# Ethernet_Phy.net
KiCad netlist of a schematic drawn in Altium Designer
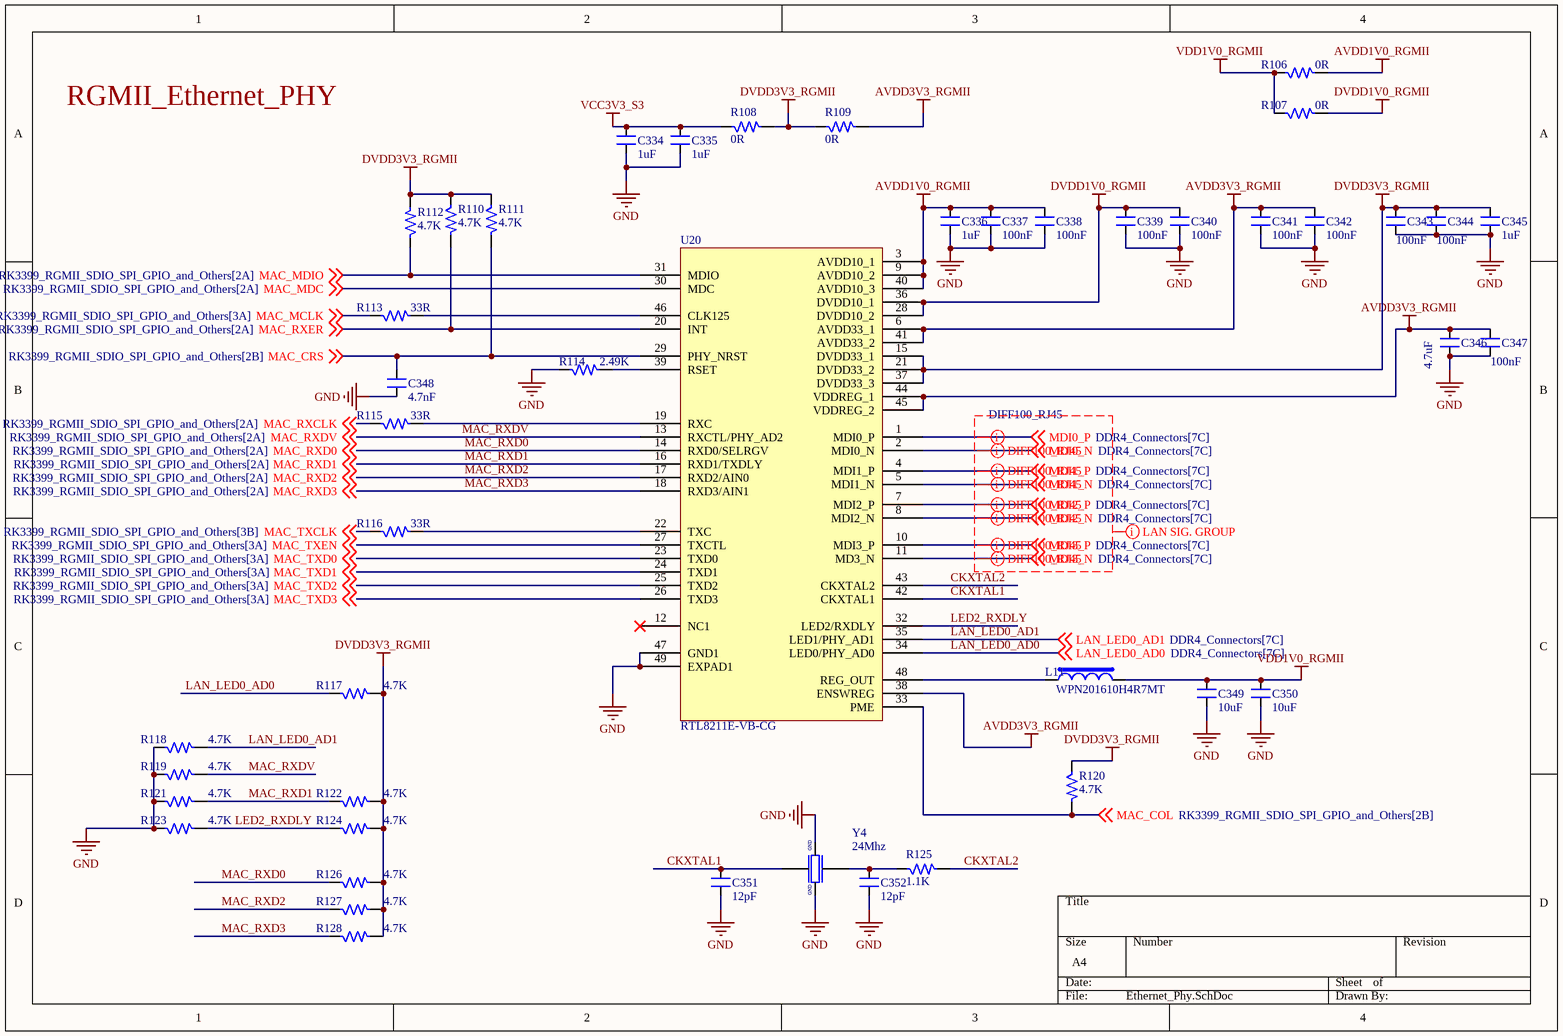
[diagram p0: Ethernet_Phy.SchDoc]

(export (version "E")
  (design (tool "Eeschema 10.0.6"))
  (components
    (comp (ref "C334")
      (value "1uF")
      (footprint "CAP_0201")
      (description "1µF ±20% 16V Ceramic Capacitor X5R 0201 (0603 Metric)")
      (fields
        (field (name "MANUFACTURER") "Samsung Electro-Mechanics")
        (field (name "MANUFACTURER PART NUMBER") "CL03A105MO3NRNH")
      )
      (libsource (lib "EsteemPCB_SOM_Course_schlib") (part "CAP_1uF-16V-10%-0201"))
    )
    (comp (ref "C335")
      (value "1uF")
      (footprint "CAP_0201")
      (description "1µF ±20% 16V Ceramic Capacitor X5R 0201 (0603 Metric)")
      (fields
        (field (name "MANUFACTURER") "Samsung Electro-Mechanics")
        (field (name "MANUFACTURER PART NUMBER") "CL03A105MO3NRNH")
      )
      (libsource (lib "EsteemPCB_SOM_Course_schlib") (part "CAP_1uF-16V-10%-0201"))
    )
    (comp (ref "C336")
      (value "1uF")
      (footprint "CAP_0201")
      (description "1µF ±20% 16V Ceramic Capacitor X5R 0201 (0603 Metric)")
      (fields
        (field (name "MANUFACTURER") "Samsung Electro-Mechanics")
        (field (name "MANUFACTURER PART NUMBER") "CL03A105MO3NRNH")
      )
      (libsource (lib "EsteemPCB_SOM_Course_schlib") (part "CAP_1uF-16V-10%-0201"))
    )
    (comp (ref "C337")
      (value "100nF")
      (footprint "CAP_0201")
      (description "0.1µF ±10% 25V Ceramic Capacitor X5R 0201 (0603 Metric)")
      (fields
        (field (name "MANUFACTURER") "TDK Corporation")
        (field (name "MANUFACTURER PART NUMBER") "C0603X5R1E104K030BB")
      )
      (libsource (lib "EsteemPCB_SOM_Course_schlib") (part "CAP_100nF-25V-10%-0201"))
    )
    (comp (ref "C338")
      (value "100nF")
      (footprint "CAP_0201")
      (description "0.1µF ±10% 25V Ceramic Capacitor X5R 0201 (0603 Metric)")
      (fields
        (field (name "MANUFACTURER") "TDK Corporation")
        (field (name "MANUFACTURER PART NUMBER") "C0603X5R1E104K030BB")
      )
      (libsource (lib "EsteemPCB_SOM_Course_schlib") (part "CAP_100nF-25V-10%-0201"))
    )
    (comp (ref "C339")
      (value "100nF")
      (footprint "CAP_0201")
      (description "0.1µF ±10% 25V Ceramic Capacitor X5R 0201 (0603 Metric)")
      (fields
        (field (name "MANUFACTURER") "TDK Corporation")
        (field (name "MANUFACTURER PART NUMBER") "C0603X5R1E104K030BB")
      )
      (libsource (lib "EsteemPCB_SOM_Course_schlib") (part "CAP_100nF-25V-10%-0201"))
    )
    (comp (ref "C340")
      (value "100nF")
      (footprint "CAP_0201")
      (description "0.1µF ±10% 25V Ceramic Capacitor X5R 0201 (0603 Metric)")
      (fields
        (field (name "MANUFACTURER") "TDK Corporation")
        (field (name "MANUFACTURER PART NUMBER") "C0603X5R1E104K030BB")
      )
      (libsource (lib "EsteemPCB_SOM_Course_schlib") (part "CAP_100nF-25V-10%-0201"))
    )
    (comp (ref "C341")
      (value "100nF")
      (footprint "CAP_0201")
      (description "0.1µF ±10% 25V Ceramic Capacitor X5R 0201 (0603 Metric)")
      (fields
        (field (name "MANUFACTURER") "TDK Corporation")
        (field (name "MANUFACTURER PART NUMBER") "C0603X5R1E104K030BB")
      )
      (libsource (lib "EsteemPCB_SOM_Course_schlib") (part "CAP_100nF-25V-10%-0201"))
    )
    (comp (ref "C342")
      (value "100nF")
      (footprint "CAP_0201")
      (description "0.1µF ±10% 25V Ceramic Capacitor X5R 0201 (0603 Metric)")
      (fields
        (field (name "MANUFACTURER") "TDK Corporation")
        (field (name "MANUFACTURER PART NUMBER") "C0603X5R1E104K030BB")
      )
      (libsource (lib "EsteemPCB_SOM_Course_schlib") (part "CAP_100nF-25V-10%-0201"))
    )
    (comp (ref "C343")
      (value "100nF")
      (footprint "CAP_0201")
      (description "0.1µF ±10% 25V Ceramic Capacitor X5R 0201 (0603 Metric)")
      (fields
        (field (name "MANUFACTURER") "TDK Corporation")
        (field (name "MANUFACTURER PART NUMBER") "C0603X5R1E104K030BB")
      )
      (libsource (lib "EsteemPCB_SOM_Course_schlib") (part "CAP_100nF-25V-10%-0201"))
    )
    (comp (ref "C344")
      (value "100nF")
      (footprint "CAP_0201")
      (description "0.1µF ±10% 25V Ceramic Capacitor X5R 0201 (0603 Metric)")
      (fields
        (field (name "MANUFACTURER") "TDK Corporation")
        (field (name "MANUFACTURER PART NUMBER") "C0603X5R1E104K030BB")
      )
      (libsource (lib "EsteemPCB_SOM_Course_schlib") (part "CAP_100nF-25V-10%-0201"))
    )
    (comp (ref "C345")
      (value "1uF")
      (footprint "CAP_0201")
      (description "1µF ±20% 16V Ceramic Capacitor X5R 0201 (0603 Metric)")
      (fields
        (field (name "MANUFACTURER") "Samsung Electro-Mechanics")
        (field (name "MANUFACTURER PART NUMBER") "CL03A105MO3NRNH")
      )
      (libsource (lib "EsteemPCB_SOM_Course_schlib") (part "CAP_1uF-16V-10%-0201"))
    )
    (comp (ref "C346")
      (value "4.7uF")
      (footprint "CAP_0201")
      (description "4.7µF ±20% 6.3V Ceramic Capacitor X5R 0201 (0603 Metric)")
      (fields
        (field (name "MANUFACTURER") "Murata Electronics")
        (field (name "MANUFACTURER PART NUMBER") "GRM035R60J475ME15D")
      )
      (libsource (lib "EsteemPCB_SOM_Course_schlib") (part "CAP_4.7uF-6.3V-20%-0201"))
    )
    (comp (ref "C347")
      (value "100nF")
      (footprint "CAP_0201")
      (description "0.1µF ±10% 25V Ceramic Capacitor X5R 0201 (0603 Metric)")
      (fields
        (field (name "MANUFACTURER") "TDK Corporation")
        (field (name "MANUFACTURER PART NUMBER") "C0603X5R1E104K030BB")
      )
      (libsource (lib "EsteemPCB_SOM_Course_schlib") (part "CAP_100nF-25V-10%-0201"))
    )
    (comp (ref "C348")
      (value "4.7nF")
      (footprint "CAP_0201")
      (description "4700pF ±10% 10V Ceramic Capacitor X7R 0201 (0603 Metric)")
      (fields
        (field (name "MANUFACTURER") "AVX Corporation")
        (field (name "MANUFACTURER PART NUMBER") "0201ZC472KAT2A")
      )
      (libsource (lib "EsteemPCB_SOM_Course_schlib") (part "CAP_4.7nF-10V-10%-0201"))
    )
    (comp (ref "C349")
      (value "10uF")
      (footprint "CAP_0402")
      (description "10µF ±20% 10V Ceramic Capacitor X5R 0402 (1005 Metric)")
      (fields
        (field (name "MANUFACTURER PART NUMBER") "CL05A106MP5NUNC")
        (field (name "MANUFACTURER") "Samsung Electro-Mechanics")
      )
      (libsource (lib "EsteemPCB_SOM_Course_schlib") (part "CAP_10uF-10V-20%-0402"))
    )
    (comp (ref "C350")
      (value "10uF")
      (footprint "CAP_0402")
      (description "10µF ±20% 10V Ceramic Capacitor X5R 0402 (1005 Metric)")
      (fields
        (field (name "MANUFACTURER PART NUMBER") "CL05A106MP5NUNC")
        (field (name "MANUFACTURER") "Samsung Electro-Mechanics")
      )
      (libsource (lib "EsteemPCB_SOM_Course_schlib") (part "CAP_10uF-10V-20%-0402"))
    )
    (comp (ref "C351")
      (value "12pF")
      (footprint "CAP_0201")
      (description "12pF ±10% 16V Ceramic Capacitor C0G, NP0 0201 (0603 Metric)")
      (fields
        (field (name "MANUFACTURER") "AVX Corporation")
        (field (name "MANUFACTURER PART NUMBER") "0201YA120KAT2A")
      )
      (libsource (lib "EsteemPCB_SOM_Course_schlib") (part "CAP_12pF-16V-10%-0201"))
    )
    (comp (ref "C352")
      (value "12pF")
      (footprint "CAP_0201")
      (description "12pF ±10% 16V Ceramic Capacitor C0G, NP0 0201 (0603 Metric)")
      (fields
        (field (name "MANUFACTURER") "AVX Corporation")
        (field (name "MANUFACTURER PART NUMBER") "0201YA120KAT2A")
      )
      (libsource (lib "EsteemPCB_SOM_Course_schlib") (part "CAP_12pF-16V-10%-0201"))
    )
    (comp (ref "L11")
      (value "WPN201610H4R7MT")
      (footprint "IND_62.9_110X86.6_SMD")
      (description "4.7uH ±20% 900mA 425mΩ SMD,2.0x1.6x1.0mm Power Inductors RoHS")
      (fields (field (name "MANUFACTURER") "Sunlord"))
      (libsource (lib "EsteemPCB_SOM_Course_schlib") (part "IND_4.7uH-0.9A-20%-SMD"))
    )
    (comp (ref "R106")
      (value "0R")
      (footprint "RES_0201")
      (description "0 Ohms Jumper 0.05W, 1/20W Chip Resistor 0201 (0603 Metric) Automotive AEC-Q200 Thick Film")
      (fields
        (field (name "MANUFACTURER") "Bourns Inc.")
        (field (name "MANUFACTURER PART NUMBER") "CR0201AJ/-000GLF")
      )
      (libsource (lib "EsteemPCB_SOM_Course_schlib") (part "RES_0R-0.05W-1%-0201"))
    )
    (comp (ref "R107")
      (value "0R")
      (footprint "RES_0201")
      (description "0 Ohms Jumper 0.05W, 1/20W Chip Resistor 0201 (0603 Metric) Automotive AEC-Q200 Thick Film")
      (fields
        (field (name "MANUFACTURER") "Bourns Inc.")
        (field (name "MANUFACTURER PART NUMBER") "CR0201AJ/-000GLF")
      )
      (libsource (lib "EsteemPCB_SOM_Course_schlib") (part "RES_0R-0.05W-1%-0201"))
    )
    (comp (ref "R108")
      (value "0R")
      (footprint "RES_0201")
      (description "0 Ohms Jumper 0.05W, 1/20W Chip Resistor 0201 (0603 Metric) Automotive AEC-Q200 Thick Film")
      (fields
        (field (name "MANUFACTURER") "Bourns Inc.")
        (field (name "MANUFACTURER PART NUMBER") "CR0201AJ/-000GLF")
      )
      (libsource (lib "EsteemPCB_SOM_Course_schlib") (part "RES_0R-0.05W-1%-0201"))
    )
    (comp (ref "R109")
      (value "0R")
      (footprint "RES_0201")
      (description "0 Ohms Jumper 0.05W, 1/20W Chip Resistor 0201 (0603 Metric) Automotive AEC-Q200 Thick Film")
      (fields
        (field (name "MANUFACTURER") "Bourns Inc.")
        (field (name "MANUFACTURER PART NUMBER") "CR0201AJ/-000GLF")
      )
      (libsource (lib "EsteemPCB_SOM_Course_schlib") (part "RES_0R-0.05W-1%-0201"))
    )
    (comp (ref "R110")
      (value "4.7K")
      (footprint "RES_0201")
      (description "4.02 kOhms ±1% 0.05W, 1/20W Chip Resistor 0201 (0603 Metric) Thick Film")
      (fields
        (field (name "MANUFACTURER") "Yageo")
        (field (name "MANUFACTURER PART NUMBER") "RC0201FR-074K02L")
      )
      (libsource (lib "EsteemPCB_SOM_Course_schlib") (part "RES_4.7K-0.1W-1%-0201"))
    )
    (comp (ref "R111")
      (value "4.7K")
      (footprint "RES_0201")
      (description "4.02 kOhms ±1% 0.05W, 1/20W Chip Resistor 0201 (0603 Metric) Thick Film")
      (fields
        (field (name "MANUFACTURER") "Yageo")
        (field (name "MANUFACTURER PART NUMBER") "RC0201FR-074K02L")
      )
      (libsource (lib "EsteemPCB_SOM_Course_schlib") (part "RES_4.7K-0.1W-1%-0201"))
    )
    (comp (ref "R112")
      (value "4.7K")
      (footprint "RES_0201")
      (description "4.02 kOhms ±1% 0.05W, 1/20W Chip Resistor 0201 (0603 Metric) Thick Film")
      (fields
        (field (name "MANUFACTURER") "Yageo")
        (field (name "MANUFACTURER PART NUMBER") "RC0201FR-074K02L")
      )
      (libsource (lib "EsteemPCB_SOM_Course_schlib") (part "RES_4.7K-0.1W-1%-0201"))
    )
    (comp (ref "R113")
      (value "33R")
      (footprint "RES_0201")
      (description "33 Ohms ±1% 0.05W, 1/20W Chip Resistor 0201 (0603 Metric) Thick Film")
      (fields
        (field (name "MANUFACTURER") "Yageo")
        (field (name "MANUFACTURER PART NUMBER") "RC0201FR-0733RL")
      )
      (libsource (lib "EsteemPCB_SOM_Course_schlib") (part "RES_33R-0.05W-1%-0201"))
    )
    (comp (ref "R114")
      (value "2.49K")
      (footprint "RES_0201")
      (description "2.49 kOhms ±1% 0.05W, 1/20W Chip Resistor 0201 (0603 Metric) Automotive AEC-Q200 Thick Film")
      (fields
        (field (name "MANUFACTURER") "Panasonic Electronic Components")
        (field (name "MANUFACTURER PART NUMBER") "ERJ-1GNF2491C")
      )
      (libsource (lib "EsteemPCB_SOM_Course_schlib") (part "RES_2.49K-0.05W-1%-0201"))
    )
    (comp (ref "R115")
      (value "33R")
      (footprint "RES_0201")
      (description "33 Ohms ±1% 0.05W, 1/20W Chip Resistor 0201 (0603 Metric) Thick Film")
      (fields
        (field (name "MANUFACTURER") "Yageo")
        (field (name "MANUFACTURER PART NUMBER") "RC0201FR-0733RL")
      )
      (libsource (lib "EsteemPCB_SOM_Course_schlib") (part "RES_33R-0.05W-1%-0201"))
    )
    (comp (ref "R116")
      (value "33R")
      (footprint "RES_0201")
      (description "33 Ohms ±1% 0.05W, 1/20W Chip Resistor 0201 (0603 Metric) Thick Film")
      (fields
        (field (name "MANUFACTURER") "Yageo")
        (field (name "MANUFACTURER PART NUMBER") "RC0201FR-0733RL")
      )
      (libsource (lib "EsteemPCB_SOM_Course_schlib") (part "RES_33R-0.05W-1%-0201"))
    )
    (comp (ref "R117")
      (value "4.7K")
      (footprint "RES_0201")
      (description "4.02 kOhms ±1% 0.05W, 1/20W Chip Resistor 0201 (0603 Metric) Thick Film")
      (fields
        (field (name "MANUFACTURER") "Yageo")
        (field (name "MANUFACTURER PART NUMBER") "RC0201FR-074K02L")
      )
      (libsource (lib "EsteemPCB_SOM_Course_schlib") (part "RES_4.7K-0.1W-1%-0201"))
    )
    (comp (ref "R118")
      (value "4.7K")
      (footprint "RES_0201")
      (description "4.02 kOhms ±1% 0.05W, 1/20W Chip Resistor 0201 (0603 Metric) Thick Film")
      (fields
        (field (name "MANUFACTURER") "Yageo")
        (field (name "MANUFACTURER PART NUMBER") "RC0201FR-074K02L")
      )
      (libsource (lib "EsteemPCB_SOM_Course_schlib") (part "RES_4.7K-0.1W-1%-0201"))
    )
    (comp (ref "R119")
      (value "4.7K")
      (footprint "RES_0201")
      (description "4.02 kOhms ±1% 0.05W, 1/20W Chip Resistor 0201 (0603 Metric) Thick Film")
      (fields
        (field (name "MANUFACTURER") "Yageo")
        (field (name "MANUFACTURER PART NUMBER") "RC0201FR-074K02L")
      )
      (libsource (lib "EsteemPCB_SOM_Course_schlib") (part "RES_4.7K-0.1W-1%-0201"))
    )
    (comp (ref "R120")
      (value "4.7K")
      (footprint "RES_0201")
      (description "4.02 kOhms ±1% 0.05W, 1/20W Chip Resistor 0201 (0603 Metric) Thick Film")
      (fields
        (field (name "MANUFACTURER") "Yageo")
        (field (name "MANUFACTURER PART NUMBER") "RC0201FR-074K02L")
      )
      (libsource (lib "EsteemPCB_SOM_Course_schlib") (part "RES_4.7K-0.1W-1%-0201"))
    )
    (comp (ref "R121")
      (value "4.7K")
      (footprint "RES_0201")
      (description "4.02 kOhms ±1% 0.05W, 1/20W Chip Resistor 0201 (0603 Metric) Thick Film")
      (fields
        (field (name "MANUFACTURER") "Yageo")
        (field (name "MANUFACTURER PART NUMBER") "RC0201FR-074K02L")
      )
      (libsource (lib "EsteemPCB_SOM_Course_schlib") (part "RES_4.7K-0.1W-1%-0201"))
    )
    (comp (ref "R122")
      (value "4.7K")
      (footprint "RES_0201")
      (description "4.02 kOhms ±1% 0.05W, 1/20W Chip Resistor 0201 (0603 Metric) Thick Film")
      (fields
        (field (name "MANUFACTURER") "Yageo")
        (field (name "MANUFACTURER PART NUMBER") "RC0201FR-074K02L")
      )
      (libsource (lib "EsteemPCB_SOM_Course_schlib") (part "RES_4.7K-0.1W-1%-0201"))
    )
    (comp (ref "R123")
      (value "4.7K")
      (footprint "RES_0201")
      (description "4.02 kOhms ±1% 0.05W, 1/20W Chip Resistor 0201 (0603 Metric) Thick Film")
      (fields
        (field (name "MANUFACTURER") "Yageo")
        (field (name "MANUFACTURER PART NUMBER") "RC0201FR-074K02L")
      )
      (libsource (lib "EsteemPCB_SOM_Course_schlib") (part "RES_4.7K-0.1W-1%-0201"))
    )
    (comp (ref "R124")
      (value "4.7K")
      (footprint "RES_0201")
      (description "4.02 kOhms ±1% 0.05W, 1/20W Chip Resistor 0201 (0603 Metric) Thick Film")
      (fields
        (field (name "MANUFACTURER") "Yageo")
        (field (name "MANUFACTURER PART NUMBER") "RC0201FR-074K02L")
      )
      (libsource (lib "EsteemPCB_SOM_Course_schlib") (part "RES_4.7K-0.1W-1%-0201"))
    )
    (comp (ref "R125")
      (value "1.1K")
      (footprint "RES_0201")
      (description "1.1 kOhms ±1% 0.05W, 1/20W Chip Resistor 0201 (0603 Metric) Automotive AEC-Q200 Thick Film")
      (fields
        (field (name "MANUFACTURER") "Panasonic Electronic Components")
        (field (name "MANUFACTURER PART NUMBER") "ERJ-1GNF1101C")
      )
      (libsource (lib "EsteemPCB_SOM_Course_schlib") (part "RES_1.1K-0.05W-1%-0201"))
    )
    (comp (ref "R126")
      (value "4.7K")
      (footprint "RES_0201")
      (description "4.02 kOhms ±1% 0.05W, 1/20W Chip Resistor 0201 (0603 Metric) Thick Film")
      (fields
        (field (name "MANUFACTURER") "Yageo")
        (field (name "MANUFACTURER PART NUMBER") "RC0201FR-074K02L")
      )
      (libsource (lib "EsteemPCB_SOM_Course_schlib") (part "RES_4.7K-0.1W-1%-0201"))
    )
    (comp (ref "R127")
      (value "4.7K")
      (footprint "RES_0201")
      (description "4.02 kOhms ±1% 0.05W, 1/20W Chip Resistor 0201 (0603 Metric) Thick Film")
      (fields
        (field (name "MANUFACTURER") "Yageo")
        (field (name "MANUFACTURER PART NUMBER") "RC0201FR-074K02L")
      )
      (libsource (lib "EsteemPCB_SOM_Course_schlib") (part "RES_4.7K-0.1W-1%-0201"))
    )
    (comp (ref "R128")
      (value "4.7K")
      (footprint "RES_0201")
      (description "4.02 kOhms ±1% 0.05W, 1/20W Chip Resistor 0201 (0603 Metric) Thick Film")
      (fields
        (field (name "MANUFACTURER") "Yageo")
        (field (name "MANUFACTURER PART NUMBER") "RC0201FR-074K02L")
      )
      (libsource (lib "EsteemPCB_SOM_Course_schlib") (part "RES_4.7K-0.1W-1%-0201"))
    )
    (comp (ref "U20")
      (value "RTL8211E-VB-CG")
      (footprint "QFN48_19.6_324X324_SMD")
      (fields (field (name "MANUFACTURER") "Realtek Semicon"))
      (libsource (lib "EsteemPCB_SOM_Course_schlib") (part "IC_RTL8211E-VB-CG"))
    )
    (comp (ref "Y4")
      (value "24Mhz")
      (footprint "XTAL_ABM8AIG-24.000MHZ-12-2Z-T3")
      (description "24MHz ±20ppm Crystal 12pF 50 Ohms 4-SMD, No Lead")
      (fields
        (field (name "MANUFACTURER") "Abracon LLC")
        (field (name "MANUFACTURER PART NUMBER") "ABM8AIG-24.000MHZ-12-2Z-T3")
      )
      (libsource (lib "EsteemPCB_SOM_Course_schlib") (part "XTAL_24Mhz-12pF-4-SMD"))
    )
  )
  (nets
    (net (code "1") (name "/CKXTAL1") (class "Default")
      (node (ref "C351") (pin "2") (pinfunction "2_2") (pintype "passive"))
      (node (ref "U20") (pin "42") (pinfunction "CKXTAL1_42") (pintype "passive"))
      (node (ref "Y4") (pin "1") (pinfunction "1_1") (pintype "passive"))
    )
    (net (code "2") (name "/CKXTAL2") (class "Default")
      (node (ref "R125") (pin "2") (pinfunction "2_2") (pintype "passive"))
      (node (ref "U20") (pin "43") (pinfunction "CKXTAL2_43") (pintype "passive"))
    )
    (net (code "3") (name "/LED2_RXDLY") (class "Default")
      (node (ref "R123") (pin "2") (pinfunction "2_2") (pintype "passive"))
      (node (ref "R124") (pin "1") (pinfunction "1_1") (pintype "passive"))
      (node (ref "U20") (pin "32") (pinfunction "LED2/RXDLY_32") (pintype "passive"))
    )
    (net (code "4") (name "AVDD1V0_RGMII") (class "Default")
      (node (ref "C336") (pin "2") (pinfunction "2_2") (pintype "passive"))
      (node (ref "C337") (pin "2") (pinfunction "2_2") (pintype "passive"))
      (node (ref "C338") (pin "2") (pinfunction "2_2") (pintype "passive"))
      (node (ref "R106") (pin "2") (pinfunction "2_2") (pintype "passive"))
      (node (ref "U20") (pin "3") (pinfunction "AVDD10_1_3") (pintype "passive"))
      (node (ref "U20") (pin "40") (pinfunction "AVDD10_3_40") (pintype "passive"))
      (node (ref "U20") (pin "9") (pinfunction "AVDD10_2_9") (pintype "passive"))
    )
    (net (code "5") (name "AVDD3V3_RGMII") (class "Default")
      (node (ref "C341") (pin "2") (pinfunction "2_2") (pintype "passive"))
      (node (ref "C342") (pin "2") (pinfunction "2_2") (pintype "passive"))
      (node (ref "C346") (pin "2") (pinfunction "2_2") (pintype "passive"))
      (node (ref "C347") (pin "2") (pinfunction "2_2") (pintype "passive"))
      (node (ref "R109") (pin "2") (pinfunction "2_2") (pintype "passive"))
      (node (ref "U20") (pin "38") (pinfunction "ENSWREG_38") (pintype "passive"))
      (node (ref "U20") (pin "41") (pinfunction "AVDD33_2_41") (pintype "passive"))
      (node (ref "U20") (pin "44") (pinfunction "VDDREG_1_44") (pintype "passive"))
      (node (ref "U20") (pin "45") (pinfunction "VDDREG_2_45") (pintype "passive"))
      (node (ref "U20") (pin "6") (pinfunction "AVDD33_1_6") (pintype "passive"))
    )
    (net (code "6") (name "DVDD1V0_RGMII") (class "Default")
      (node (ref "C339") (pin "2") (pinfunction "2_2") (pintype "passive"))
      (node (ref "C340") (pin "2") (pinfunction "2_2") (pintype "passive"))
      (node (ref "R107") (pin "2") (pinfunction "2_2") (pintype "passive"))
      (node (ref "U20") (pin "28") (pinfunction "DVDD10_2_28") (pintype "passive"))
      (node (ref "U20") (pin "36") (pinfunction "DVDD10_1_36") (pintype "passive"))
    )
    (net (code "7") (name "DVDD3V3_RGMII") (class "Default")
      (node (ref "C343") (pin "2") (pinfunction "2_2") (pintype "passive"))
      (node (ref "C344") (pin "2") (pinfunction "2_2") (pintype "passive"))
      (node (ref "C345") (pin "2") (pinfunction "2_2") (pintype "passive"))
      (node (ref "R108") (pin "2") (pinfunction "2_2") (pintype "passive"))
      (node (ref "R109") (pin "1") (pinfunction "1_1") (pintype "passive"))
      (node (ref "R110") (pin "1") (pinfunction "1_1") (pintype "passive"))
      (node (ref "R111") (pin "1") (pinfunction "1_1") (pintype "passive"))
      (node (ref "R112") (pin "2") (pinfunction "2_2") (pintype "passive"))
      (node (ref "R117") (pin "2") (pinfunction "2_2") (pintype "passive"))
      (node (ref "R120") (pin "1") (pinfunction "1_1") (pintype "passive"))
      (node (ref "R122") (pin "2") (pinfunction "2_2") (pintype "passive"))
      (node (ref "R124") (pin "2") (pinfunction "2_2") (pintype "passive"))
      (node (ref "R126") (pin "2") (pinfunction "2_2") (pintype "passive"))
      (node (ref "R127") (pin "2") (pinfunction "2_2") (pintype "passive"))
      (node (ref "R128") (pin "2") (pinfunction "2_2") (pintype "passive"))
      (node (ref "U20") (pin "15") (pinfunction "DVDD33_1_15") (pintype "passive"))
      (node (ref "U20") (pin "21") (pinfunction "DVDD33_2_21") (pintype "passive"))
      (node (ref "U20") (pin "37") (pinfunction "DVDD33_3_37") (pintype "passive"))
    )
    (net (code "8") (name "GND") (class "Default")
      (node (ref "C334") (pin "1") (pinfunction "1_1") (pintype "passive"))
      (node (ref "C335") (pin "1") (pinfunction "1_1") (pintype "passive"))
      (node (ref "C336") (pin "1") (pinfunction "1_1") (pintype "passive"))
      (node (ref "C337") (pin "1") (pinfunction "1_1") (pintype "passive"))
      (node (ref "C338") (pin "1") (pinfunction "1_1") (pintype "passive"))
      (node (ref "C339") (pin "1") (pinfunction "1_1") (pintype "passive"))
      (node (ref "C340") (pin "1") (pinfunction "1_1") (pintype "passive"))
      (node (ref "C341") (pin "1") (pinfunction "1_1") (pintype "passive"))
      (node (ref "C342") (pin "1") (pinfunction "1_1") (pintype "passive"))
      (node (ref "C343") (pin "1") (pinfunction "1_1") (pintype "passive"))
      (node (ref "C344") (pin "1") (pinfunction "1_1") (pintype "passive"))
      (node (ref "C345") (pin "1") (pinfunction "1_1") (pintype "passive"))
      (node (ref "C346") (pin "1") (pinfunction "1_1") (pintype "passive"))
      (node (ref "C347") (pin "1") (pinfunction "1_1") (pintype "passive"))
      (node (ref "C348") (pin "1") (pinfunction "1_1") (pintype "passive"))
      (node (ref "C349") (pin "1") (pinfunction "1_1") (pintype "passive"))
      (node (ref "C350") (pin "1") (pinfunction "1_1") (pintype "passive"))
      (node (ref "C351") (pin "1") (pinfunction "1_1") (pintype "passive"))
      (node (ref "C352") (pin "1") (pinfunction "1_1") (pintype "passive"))
      (node (ref "R114") (pin "1") (pinfunction "1_1") (pintype "passive"))
      (node (ref "R118") (pin "1") (pinfunction "1_1") (pintype "passive"))
      (node (ref "R119") (pin "1") (pinfunction "1_1") (pintype "passive"))
      (node (ref "R121") (pin "1") (pinfunction "1_1") (pintype "passive"))
      (node (ref "R123") (pin "1") (pinfunction "1_1") (pintype "passive"))
      (node (ref "U20") (pin "47") (pinfunction "GND1_47") (pintype "passive"))
      (node (ref "U20") (pin "49") (pinfunction "EXPAD1_49") (pintype "passive"))
      (node (ref "Y4") (pin "2") (pinfunction "2_2") (pintype "passive"))
      (node (ref "Y4") (pin "4") (pinfunction "4_4") (pintype "passive"))
    )
    (net (code "9") (name "LAN_LED0_AD0") (class "Default")
      (node (ref "R117") (pin "1") (pinfunction "1_1") (pintype "passive"))
      (node (ref "U20") (pin "34") (pinfunction "LED0/PHY_AD0_34") (pintype "passive"))
    )
    (net (code "10") (name "LAN_LED0_AD1") (class "Default")
      (node (ref "R118") (pin "2") (pinfunction "2_2") (pintype "passive"))
      (node (ref "U20") (pin "35") (pinfunction "LED1/PHY_AD1_35") (pintype "passive"))
    )
    (net (code "11") (name "MAC_COL") (class "Default")
      (node (ref "R120") (pin "2") (pinfunction "2_2") (pintype "passive"))
      (node (ref "U20") (pin "33") (pinfunction "PME_33") (pintype "passive"))
    )
    (net (code "12") (name "MAC_CRS") (class "Default")
      (node (ref "C348") (pin "2") (pinfunction "2_2") (pintype "passive"))
      (node (ref "R111") (pin "2") (pinfunction "2_2") (pintype "passive"))
      (node (ref "U20") (pin "29") (pinfunction "PHY_NRST_29") (pintype "passive"))
    )
    (net (code "13") (name "MAC_MCLK") (class "Default")
      (node (ref "R113") (pin "1") (pinfunction "1_1") (pintype "passive"))
    )
    (net (code "14") (name "MAC_MDC") (class "Default")
      (node (ref "U20") (pin "30") (pinfunction "MDC_30") (pintype "passive"))
    )
    (net (code "15") (name "MAC_MDIO") (class "Default")
      (node (ref "R112") (pin "1") (pinfunction "1_1") (pintype "passive"))
      (node (ref "U20") (pin "31") (pinfunction "MDIO_31") (pintype "passive"))
    )
    (net (code "16") (name "MAC_RXCLK") (class "Default")
      (node (ref "R115") (pin "1") (pinfunction "1_1") (pintype "passive"))
    )
    (net (code "17") (name "MAC_RXD0") (class "Default")
      (node (ref "R126") (pin "1") (pinfunction "1_1") (pintype "passive"))
      (node (ref "U20") (pin "14") (pinfunction "RXD0/SELRGV_14") (pintype "passive"))
    )
    (net (code "18") (name "MAC_RXD1") (class "Default")
      (node (ref "R121") (pin "2") (pinfunction "2_2") (pintype "passive"))
      (node (ref "R122") (pin "1") (pinfunction "1_1") (pintype "passive"))
      (node (ref "U20") (pin "16") (pinfunction "RXD1/TXDLY_16") (pintype "passive"))
    )
    (net (code "19") (name "MAC_RXD2") (class "Default")
      (node (ref "R127") (pin "1") (pinfunction "1_1") (pintype "passive"))
      (node (ref "U20") (pin "17") (pinfunction "RXD2/AIN0_17") (pintype "passive"))
    )
    (net (code "20") (name "MAC_RXD3") (class "Default")
      (node (ref "R128") (pin "1") (pinfunction "1_1") (pintype "passive"))
      (node (ref "U20") (pin "18") (pinfunction "RXD3/AIN1_18") (pintype "passive"))
    )
    (net (code "21") (name "MAC_RXDV") (class "Default")
      (node (ref "R119") (pin "2") (pinfunction "2_2") (pintype "passive"))
      (node (ref "U20") (pin "13") (pinfunction "RXCTL/PHY_AD2_13") (pintype "passive"))
    )
    (net (code "22") (name "MAC_RXER") (class "Default")
      (node (ref "R110") (pin "2") (pinfunction "2_2") (pintype "passive"))
      (node (ref "U20") (pin "20") (pinfunction "INT_20") (pintype "passive"))
    )
    (net (code "23") (name "MAC_TXCLK") (class "Default")
      (node (ref "R116") (pin "1") (pinfunction "1_1") (pintype "passive"))
    )
    (net (code "24") (name "MAC_TXD0") (class "Default")
      (node (ref "U20") (pin "23") (pinfunction "TXD0_23") (pintype "passive"))
    )
    (net (code "25") (name "MAC_TXD1") (class "Default")
      (node (ref "U20") (pin "24") (pinfunction "TXD1_24") (pintype "passive"))
    )
    (net (code "26") (name "MAC_TXD2") (class "Default")
      (node (ref "U20") (pin "25") (pinfunction "TXD2_25") (pintype "passive"))
    )
    (net (code "27") (name "MAC_TXD3") (class "Default")
      (node (ref "U20") (pin "26") (pinfunction "TXD3_26") (pintype "passive"))
    )
    (net (code "28") (name "MAC_TXEN") (class "Default")
      (node (ref "U20") (pin "27") (pinfunction "TXCTL_27") (pintype "passive"))
    )
    (net (code "29") (name "MDI0_N") (class "Default")
      (node (ref "U20") (pin "2") (pinfunction "MDI0_N_2") (pintype "passive"))
    )
    (net (code "30") (name "MDI0_P") (class "Default")
      (node (ref "U20") (pin "1") (pinfunction "MDI0_P_1") (pintype "passive"))
    )
    (net (code "31") (name "MDI1_N") (class "Default")
      (node (ref "U20") (pin "5") (pinfunction "MDI1_N_5") (pintype "passive"))
    )
    (net (code "32") (name "MDI1_P") (class "Default")
      (node (ref "U20") (pin "4") (pinfunction "MDI1_P_4") (pintype "passive"))
    )
    (net (code "33") (name "MDI2_N") (class "Default")
      (node (ref "U20") (pin "8") (pinfunction "MDI2_N_8") (pintype "passive"))
    )
    (net (code "34") (name "MDI2_P") (class "Default")
      (node (ref "U20") (pin "7") (pinfunction "MDI2_P_7") (pintype "passive"))
    )
    (net (code "35") (name "MDI3_N") (class "Default")
      (node (ref "U20") (pin "11") (pinfunction "MD3_N_11") (pintype "passive"))
    )
    (net (code "36") (name "MDI3_P") (class "Default")
      (node (ref "U20") (pin "10") (pinfunction "MDI3_P_10") (pintype "passive"))
    )
    (net (code "37") (name "Net-(C352-Pad2)") (class "Default")
      (node (ref "C352") (pin "2") (pinfunction "2_2") (pintype "passive"))
      (node (ref "R125") (pin "1") (pinfunction "1_1") (pintype "passive"))
      (node (ref "Y4") (pin "3") (pinfunction "3_3") (pintype "passive"))
    )
    (net (code "38") (name "Net-(U20-CLK125)") (class "Default")
      (node (ref "R113") (pin "2") (pinfunction "2_2") (pintype "passive"))
      (node (ref "U20") (pin "46") (pinfunction "CLK125_46") (pintype "passive"))
    )
    (net (code "39") (name "Net-(U20-REG_OUT)") (class "Default")
      (node (ref "L11") (pin "1") (pinfunction "1_1") (pintype "passive"))
      (node (ref "U20") (pin "48") (pinfunction "REG_OUT_48") (pintype "passive"))
    )
    (net (code "40") (name "Net-(U20-RSET)") (class "Default")
      (node (ref "R114") (pin "2") (pinfunction "2_2") (pintype "passive"))
      (node (ref "U20") (pin "39") (pinfunction "RSET_39") (pintype "passive"))
    )
    (net (code "41") (name "Net-(U20-RXC)") (class "Default")
      (node (ref "R115") (pin "2") (pinfunction "2_2") (pintype "passive"))
      (node (ref "U20") (pin "19") (pinfunction "RXC_19") (pintype "passive"))
    )
    (net (code "42") (name "Net-(U20-TXC)") (class "Default")
      (node (ref "R116") (pin "2") (pinfunction "2_2") (pintype "passive"))
      (node (ref "U20") (pin "22") (pinfunction "TXC_22") (pintype "passive"))
    )
    (net (code "43") (name "VCC3V3_S3") (class "Default")
      (node (ref "C334") (pin "2") (pinfunction "2_2") (pintype "passive"))
      (node (ref "C335") (pin "2") (pinfunction "2_2") (pintype "passive"))
      (node (ref "R108") (pin "1") (pinfunction "1_1") (pintype "passive"))
    )
    (net (code "44") (name "VDD1V0_RGMII") (class "Default")
      (node (ref "C349") (pin "2") (pinfunction "2_2") (pintype "passive"))
      (node (ref "C350") (pin "2") (pinfunction "2_2") (pintype "passive"))
      (node (ref "L11") (pin "2") (pinfunction "2_2") (pintype "passive"))
      (node (ref "R106") (pin "1") (pinfunction "1_1") (pintype "passive"))
      (node (ref "R107") (pin "1") (pinfunction "1_1") (pintype "passive"))
    )
    (net (code "45") (name "unconnected-(U20-NC1-Pad12)") (class "Default")
      (node (ref "U20") (pin "12") (pinfunction "NC1_12") (pintype "passive+no_connect"))
    )
  )
)
